# rat2b.net
KiCad netlist of a schematic drawn in EAGLE
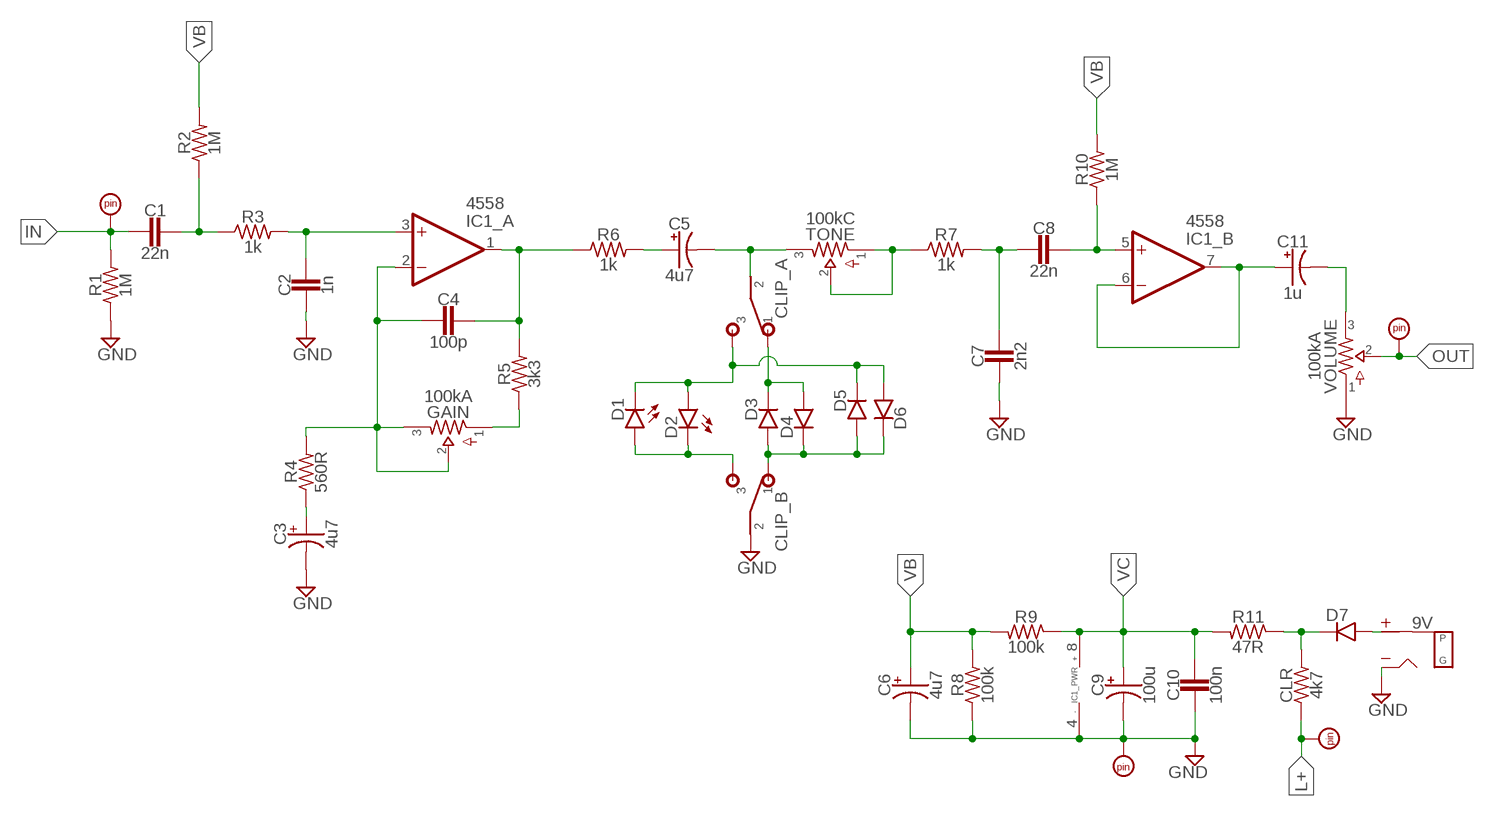
[diagram p0: schematic, sheet 1]

(export (version "E")
  (design (tool "Eeschema 10.0.6"))
  (components
    (comp (ref "9V")
      (value "DC_MONO")
      (footprint "eagle-import:DC")
      (libsource (lib "eagle-import") (part "DC_MONO"))
    )
    (comp (ref "C1")
      (value "22n")
      (footprint "eagle-import:050X030_025_2")
      (libsource (lib "eagle-import") (part "CER/FILM2"))
    )
    (comp (ref "C2")
      (value "1n")
      (footprint "eagle-import:050X030_025_2")
      (libsource (lib "eagle-import") (part "CER/FILM2"))
    )
    (comp (ref "C3")
      (value "4u7")
      (footprint "eagle-import:050_020_1")
      (libsource (lib "eagle-import") (part "0501"))
    )
    (comp (ref "C4")
      (value "100p")
      (footprint "eagle-import:050X030_025_2")
      (libsource (lib "eagle-import") (part "CER/FILM2"))
    )
    (comp (ref "C5")
      (value "4u7")
      (footprint "eagle-import:050_020_1")
      (libsource (lib "eagle-import") (part "0501"))
    )
    (comp (ref "C6")
      (value "4u7")
      (footprint "eagle-import:050_020_1")
      (libsource (lib "eagle-import") (part "0501"))
    )
    (comp (ref "C7")
      (value "2n2")
      (footprint "eagle-import:050X030_025_2")
      (libsource (lib "eagle-import") (part "CER/FILM2"))
    )
    (comp (ref "C8")
      (value "22n")
      (footprint "eagle-import:050X030_025_2")
      (libsource (lib "eagle-import") (part "CER/FILM2"))
    )
    (comp (ref "C9")
      (value "100u")
      (footprint "eagle-import:050_020_1")
      (libsource (lib "eagle-import") (part "0501"))
    )
    (comp (ref "C10")
      (value "100n")
      (footprint "eagle-import:050X030_025_2")
      (libsource (lib "eagle-import") (part "CER/FILM2"))
    )
    (comp (ref "C11")
      (value "1u")
      (footprint "eagle-import:050_020_1")
      (libsource (lib "eagle-import") (part "0501"))
    )
    (comp (ref "CLIP")
      (value "DPDTPCB")
      (footprint "eagle-import:DPDT2_PCB")
      (libsource (lib "eagle-import") (part "DPDTPCB"))
    )
    (comp (ref "CLR")
      (value "4k7")
      (footprint "eagle-import:R0207_3")
      (libsource (lib "eagle-import") (part "R_.3B"))
    )
    (comp (ref "D1")
      (value "LEDB")
      (footprint "eagle-import:3MM_B")
      (libsource (lib "eagle-import") (part "LEDB"))
    )
    (comp (ref "D2")
      (value "LEDB")
      (footprint "eagle-import:3MM_B")
      (libsource (lib "eagle-import") (part "LEDB"))
    )
    (comp (ref "D3")
      (value "DO35.3")
      (footprint "eagle-import:DO35-3")
      (libsource (lib "eagle-import") (part "DO35.3"))
    )
    (comp (ref "D4")
      (value "DO35.3")
      (footprint "eagle-import:DO35-3")
      (libsource (lib "eagle-import") (part "DO35.3"))
    )
    (comp (ref "D5")
      (value "DO35.2")
      (footprint "eagle-import:DO35-2")
      (libsource (lib "eagle-import") (part "DO35.2"))
    )
    (comp (ref "D6")
      (value "DO35.2")
      (footprint "eagle-import:DO35-2")
      (libsource (lib "eagle-import") (part "DO35.2"))
    )
    (comp (ref "D7")
      (value "DO41.3")
      (footprint "eagle-import:DO41-3")
      (libsource (lib "eagle-import") (part "DO41.3"))
    )
    (comp (ref "GAIN")
      (value "100kA")
      (footprint "eagle-import:16MM")
      (libsource (lib "eagle-import") (part "POTS16MM"))
    )
    (comp (ref "GND")
      (value "PADRND")
      (footprint "eagle-import:ROUND")
      (libsource (lib "eagle-import") (part "PADRND"))
    )
    (comp (ref "IC1")
      (value "4558")
      (footprint "eagle-import:DIL08")
      (libsource (lib "eagle-import") (part "DUALTH"))
    )
    (comp (ref "IN")
      (value "PADSQR")
      (footprint "eagle-import:SQUARE")
      (libsource (lib "eagle-import") (part "PADSQR"))
    )
    (comp (ref "LED")
      (value "PADSQR")
      (footprint "eagle-import:SQUARE")
      (libsource (lib "eagle-import") (part "PADSQR"))
    )
    (comp (ref "OUT")
      (value "PADSQR")
      (footprint "eagle-import:SQUARE")
      (libsource (lib "eagle-import") (part "PADSQR"))
    )
    (comp (ref "R1")
      (value "1M")
      (footprint "eagle-import:R0207_3")
      (libsource (lib "eagle-import") (part "R_.3B"))
    )
    (comp (ref "R2")
      (value "1M")
      (footprint "eagle-import:R0207_3")
      (libsource (lib "eagle-import") (part "R_.3B"))
    )
    (comp (ref "R3")
      (value "1k")
      (footprint "eagle-import:R0207_3")
      (libsource (lib "eagle-import") (part "R_.3B"))
    )
    (comp (ref "R4")
      (value "560R")
      (footprint "eagle-import:R0207_3")
      (libsource (lib "eagle-import") (part "R_.3B"))
    )
    (comp (ref "R5")
      (value "3k3")
      (footprint "eagle-import:R0207_3")
      (libsource (lib "eagle-import") (part "R_.3B"))
    )
    (comp (ref "R6")
      (value "1k")
      (footprint "eagle-import:R0207_3")
      (libsource (lib "eagle-import") (part "R_.3B"))
    )
    (comp (ref "R7")
      (value "1k")
      (footprint "eagle-import:R0207_3")
      (libsource (lib "eagle-import") (part "R_.3B"))
    )
    (comp (ref "R8")
      (value "100k")
      (footprint "eagle-import:R0207_3")
      (libsource (lib "eagle-import") (part "R_.3B"))
    )
    (comp (ref "R9")
      (value "100k")
      (footprint "eagle-import:R0207_3")
      (libsource (lib "eagle-import") (part "R_.3B"))
    )
    (comp (ref "R10")
      (value "1M")
      (footprint "eagle-import:R0207_3")
      (libsource (lib "eagle-import") (part "R_.3B"))
    )
    (comp (ref "R11")
      (value "47R")
      (footprint "eagle-import:R0207_3")
      (libsource (lib "eagle-import") (part "R_.3B"))
    )
    (comp (ref "TONE")
      (value "100kC")
      (footprint "eagle-import:16MM")
      (libsource (lib "eagle-import") (part "POTS16MM"))
    )
    (comp (ref "VOLUME")
      (value "100kA")
      (footprint "eagle-import:16MM")
      (libsource (lib "eagle-import") (part "POTS16MM"))
    )
  )
  (nets
    (net (code "1") (name "GND") (class "Default")
      (node (ref "9V") (pin "S") (pinfunction "SLEEVE_S") (pintype "passive"))
      (node (ref "C10") (pin "2") (pinfunction "2_2") (pintype "passive"))
      (node (ref "C2") (pin "2") (pinfunction "2_2") (pintype "passive"))
      (node (ref "C3") (pin "-") (pinfunction "-_-") (pintype "passive"))
      (node (ref "C6") (pin "-") (pinfunction "-_-") (pintype "passive"))
      (node (ref "C7") (pin "2") (pinfunction "2_2") (pintype "passive"))
      (node (ref "C9") (pin "-") (pinfunction "-_-") (pintype "passive"))
      (node (ref "CLIP") (pin "B2") (pinfunction "2_B2") (pintype "passive"))
      (node (ref "GND") (pin "1") (pinfunction "P$1_1") (pintype "bidirectional"))
      (node (ref "IC1") (pin "4") (pinfunction "V-_4") (pintype "power_in"))
      (node (ref "R1") (pin "1") (pinfunction "1_1") (pintype "passive"))
      (node (ref "R8") (pin "1") (pinfunction "1_1") (pintype "passive"))
      (node (ref "VOLUME") (pin "1") (pinfunction "1_1") (pintype "passive"))
    )
    (net (code "2") (name "IN") (class "Default")
      (node (ref "C1") (pin "2") (pinfunction "2_2") (pintype "passive"))
      (node (ref "IN") (pin "1") (pinfunction "P$1_1") (pintype "bidirectional"))
      (node (ref "R1") (pin "2") (pinfunction "2_2") (pintype "passive"))
    )
    (net (code "3") (name "L+") (class "Default")
      (node (ref "CLR") (pin "1") (pinfunction "1_1") (pintype "passive"))
      (node (ref "CLR") (pin "2") (pinfunction "2_2") (pintype "passive"))
      (node (ref "D7") (pin "C") (pinfunction "C_C") (pintype "passive"))
      (node (ref "LED") (pin "1") (pinfunction "P$1_1") (pintype "bidirectional"))
      (node (ref "R11") (pin "1") (pinfunction "1_1") (pintype "passive"))
    )
    (net (code "4") (name "Net-(9V-TIP)") (class "Default")
      (node (ref "9V") (pin "T") (pinfunction "TIP_T") (pintype "passive"))
      (node (ref "D7") (pin "A") (pinfunction "A_A") (pintype "passive"))
    )
    (net (code "5") (name "Net-(C1-Pad1)") (class "Default")
      (node (ref "C1") (pin "1") (pinfunction "1_1") (pintype "passive"))
      (node (ref "R2") (pin "1") (pinfunction "1_1") (pintype "passive"))
      (node (ref "R3") (pin "1") (pinfunction "1_1") (pintype "passive"))
    )
    (net (code "6") (name "Net-(C3-Pad+)") (class "Default")
      (node (ref "C3") (pin "+") (pinfunction "+_+") (pintype "passive"))
      (node (ref "R4") (pin "1") (pinfunction "1_1") (pintype "passive"))
    )
    (net (code "7") (name "Net-(C5-Pad+)") (class "Default")
      (node (ref "C5") (pin "+") (pinfunction "+_+") (pintype "passive"))
      (node (ref "R6") (pin "2") (pinfunction "2_2") (pintype "passive"))
    )
    (net (code "8") (name "Net-(C7-Pad1)") (class "Default")
      (node (ref "C7") (pin "1") (pinfunction "1_1") (pintype "passive"))
      (node (ref "C8") (pin "2") (pinfunction "2_2") (pintype "passive"))
      (node (ref "R7") (pin "2") (pinfunction "2_2") (pintype "passive"))
    )
    (net (code "9") (name "Net-(C11-Pad-)") (class "Default")
      (node (ref "C11") (pin "-") (pinfunction "-_-") (pintype "passive"))
      (node (ref "VOLUME") (pin "3") (pinfunction "3_3") (pintype "passive"))
    )
    (net (code "10") (name "Net-(CLIPA-1)") (class "Default")
      (node (ref "CLIP") (pin "A1") (pinfunction "1_A1") (pintype "passive"))
      (node (ref "D3") (pin "C") (pinfunction "C_C") (pintype "passive"))
      (node (ref "D4") (pin "A") (pinfunction "A_A") (pintype "passive"))
    )
    (net (code "11") (name "Net-(CLIPA-2)") (class "Default")
      (node (ref "C5") (pin "-") (pinfunction "-_-") (pintype "passive"))
      (node (ref "CLIP") (pin "A2") (pinfunction "2_A2") (pintype "passive"))
      (node (ref "TONE") (pin "3") (pinfunction "3_3") (pintype "passive"))
    )
    (net (code "12") (name "Net-(CLIPA-3)") (class "Default")
      (node (ref "CLIP") (pin "A3") (pinfunction "3_A3") (pintype "passive"))
      (node (ref "D1") (pin "K") (pinfunction "C_K") (pintype "passive"))
      (node (ref "D2") (pin "A") (pinfunction "A_A") (pintype "passive"))
      (node (ref "D5") (pin "C") (pinfunction "C_C") (pintype "passive"))
      (node (ref "D6") (pin "A") (pinfunction "A_A") (pintype "passive"))
    )
    (net (code "13") (name "Net-(CLIPB-1)") (class "Default")
      (node (ref "CLIP") (pin "B1") (pinfunction "1_B1") (pintype "passive"))
      (node (ref "D3") (pin "A") (pinfunction "A_A") (pintype "passive"))
      (node (ref "D4") (pin "C") (pinfunction "C_C") (pintype "passive"))
      (node (ref "D5") (pin "A") (pinfunction "A_A") (pintype "passive"))
      (node (ref "D6") (pin "C") (pinfunction "C_C") (pintype "passive"))
    )
    (net (code "14") (name "Net-(CLIPB-3)") (class "Default")
      (node (ref "CLIP") (pin "B3") (pinfunction "3_B3") (pintype "passive"))
      (node (ref "D1") (pin "A") (pinfunction "A_A") (pintype "passive"))
      (node (ref "D2") (pin "K") (pinfunction "C_K") (pintype "passive"))
    )
    (net (code "15") (name "Net-(GAIN-Pad1)") (class "Default")
      (node (ref "GAIN") (pin "1") (pinfunction "1_1") (pintype "passive"))
      (node (ref "R5") (pin "1") (pinfunction "1_1") (pintype "passive"))
    )
    (net (code "16") (name "Net-(IC1A-+IN)") (class "Default")
      (node (ref "C2") (pin "1") (pinfunction "1_1") (pintype "passive"))
      (node (ref "IC1") (pin "3") (pinfunction "+IN_3") (pintype "input"))
      (node (ref "R3") (pin "2") (pinfunction "2_2") (pintype "passive"))
    )
    (net (code "17") (name "Net-(IC1A--IN)") (class "Default")
      (node (ref "C4") (pin "2") (pinfunction "2_2") (pintype "passive"))
      (node (ref "GAIN") (pin "2") (pinfunction "2_2") (pintype "passive"))
      (node (ref "GAIN") (pin "3") (pinfunction "3_3") (pintype "passive"))
      (node (ref "IC1") (pin "2") (pinfunction "-IN_2") (pintype "input"))
      (node (ref "R4") (pin "2") (pinfunction "2_2") (pintype "passive"))
    )
    (net (code "18") (name "Net-(IC1A-OUT)") (class "Default")
      (node (ref "C4") (pin "1") (pinfunction "1_1") (pintype "passive"))
      (node (ref "IC1") (pin "1") (pinfunction "OUT_1") (pintype "output"))
      (node (ref "R5") (pin "2") (pinfunction "2_2") (pintype "passive"))
      (node (ref "R6") (pin "1") (pinfunction "1_1") (pintype "passive"))
    )
    (net (code "19") (name "Net-(IC1B-+IN)") (class "Default")
      (node (ref "C8") (pin "1") (pinfunction "1_1") (pintype "passive"))
      (node (ref "IC1") (pin "5") (pinfunction "+IN_5") (pintype "input"))
      (node (ref "R10") (pin "1") (pinfunction "1_1") (pintype "passive"))
    )
    (net (code "20") (name "Net-(IC1B--IN)") (class "Default")
      (node (ref "C11") (pin "+") (pinfunction "+_+") (pintype "passive"))
      (node (ref "IC1") (pin "6") (pinfunction "-IN_6") (pintype "input"))
      (node (ref "IC1") (pin "7") (pinfunction "OUT_7") (pintype "output"))
    )
    (net (code "21") (name "Net-(R7-Pad1)") (class "Default")
      (node (ref "R7") (pin "1") (pinfunction "1_1") (pintype "passive"))
      (node (ref "TONE") (pin "1") (pinfunction "1_1") (pintype "passive"))
      (node (ref "TONE") (pin "2") (pinfunction "2_2") (pintype "passive"))
    )
    (net (code "22") (name "OUT") (class "Default")
      (node (ref "OUT") (pin "1") (pinfunction "P$1_1") (pintype "bidirectional"))
      (node (ref "VOLUME") (pin "2") (pinfunction "2_2") (pintype "passive"))
    )
    (net (code "23") (name "VB") (class "Default")
      (node (ref "C6") (pin "+") (pinfunction "+_+") (pintype "passive"))
      (node (ref "R10") (pin "2") (pinfunction "2_2") (pintype "passive"))
      (node (ref "R2") (pin "2") (pinfunction "2_2") (pintype "passive"))
      (node (ref "R8") (pin "2") (pinfunction "2_2") (pintype "passive"))
      (node (ref "R9") (pin "2") (pinfunction "2_2") (pintype "passive"))
    )
    (net (code "24") (name "VC") (class "Default")
      (node (ref "C10") (pin "1") (pinfunction "1_1") (pintype "passive"))
      (node (ref "C9") (pin "+") (pinfunction "+_+") (pintype "passive"))
      (node (ref "IC1") (pin "8") (pinfunction "V+_8") (pintype "power_in"))
      (node (ref "R11") (pin "2") (pinfunction "2_2") (pintype "passive"))
      (node (ref "R9") (pin "1") (pinfunction "1_1") (pintype "passive"))
    )
  )
)
